# Sheet3.net
KiCad netlist of a schematic drawn in Altium Designer
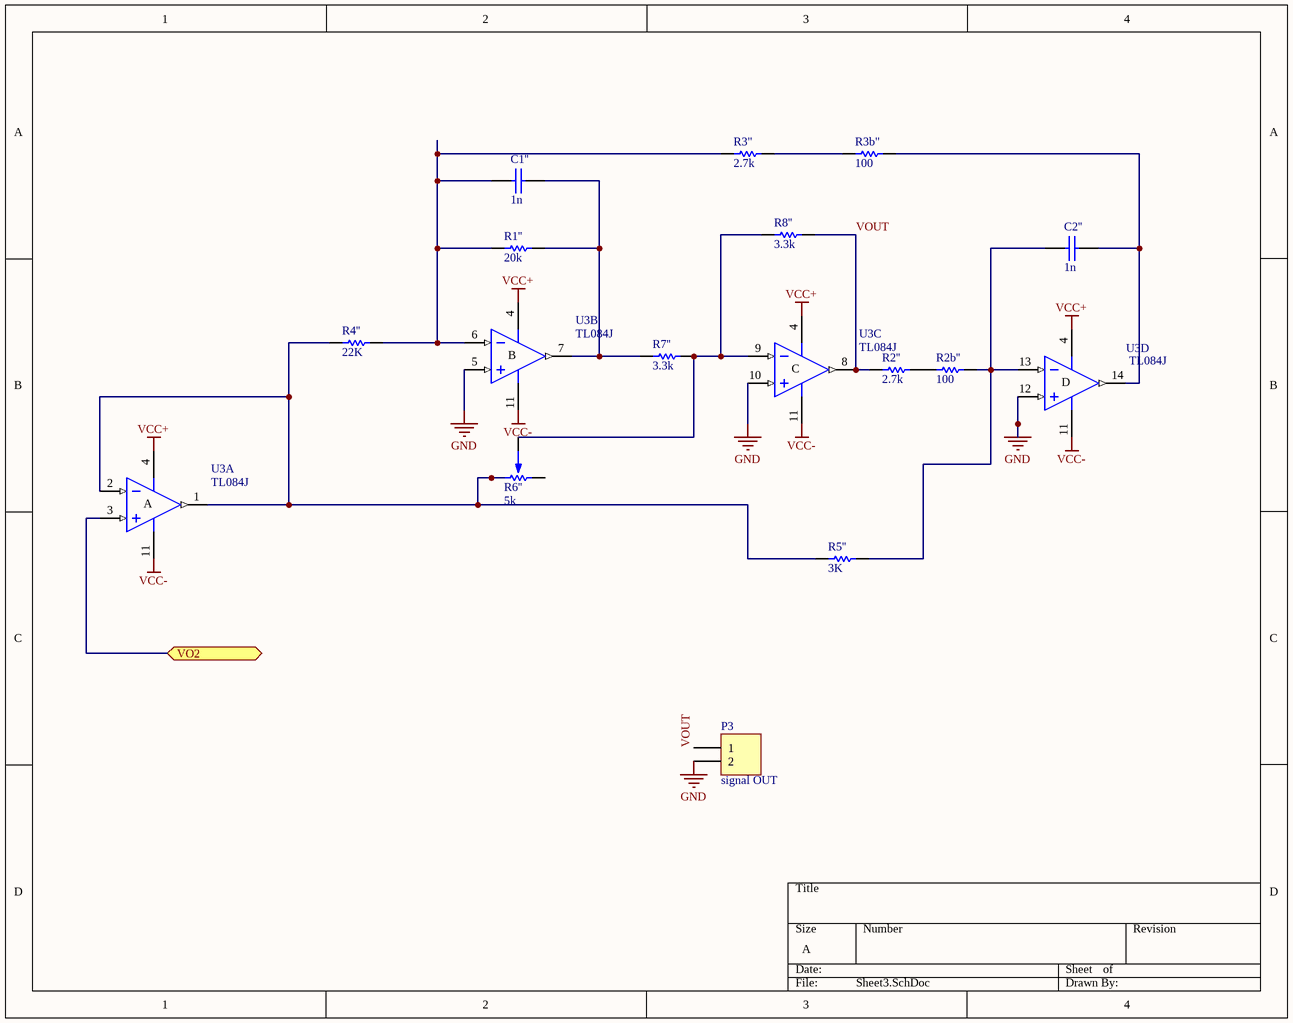
[diagram p0: Sheet3.SchDoc]

(export (version "E")
  (design (tool "Eeschema 10.0.6"))
  (components
    (comp (ref "C1''") (value "1n") (footprint "CAP100") (libsource (lib "LIBEBAL") (part "CAP")))
    (comp (ref "C2''") (value "1n") (footprint "CAP100") (libsource (lib "LIBEBAL") (part "CAP")))
    (comp (ref "P3")
      (value "signal OUT")
      (footprint "HDR1X2")
      (description "Header, 2-Pin")
      (fields (field (name "PUBLISHER") "Altium Limited"))
      (libsource (lib "Miscellaneous Connectors") (part "Header 2"))
    )
    (comp (ref "R1''") (value "20k") (footprint "0805") (libsource (lib "LIBEBAL") (part "RES")))
    (comp (ref "R2''") (value "2.7k") (footprint "0805") (libsource (lib "LIBEBAL") (part "RES")))
    (comp (ref "R2b''") (value "100") (footprint "0805") (libsource (lib "LIBEBAL") (part "RES")))
    (comp (ref "R3\"") (value "2.7k") (footprint "0805") (libsource (lib "LIBEBAL") (part "RES")))
    (comp (ref "R3b\"") (value "100") (footprint "0805") (libsource (lib "LIBEBAL") (part "RES")))
    (comp (ref "R4''") (value "22K") (footprint "0805") (libsource (lib "LIBEBAL") (part "RES")))
    (comp (ref "R5''") (value "3K") (footprint "0805") (libsource (lib "LIBEBAL") (part "RES")))
    (comp (ref "R6''") (value "5k") (footprint "PRESET V") (libsource (lib "LIBEBAL") (part "PRESET")))
    (comp (ref "R7''") (value "3.3k") (footprint "0805") (libsource (lib "LIBEBAL") (part "RES")))
    (comp (ref "R8''") (value "3.3k") (footprint "0805") (libsource (lib "LIBEBAL") (part "RES")))
    (comp (ref "U3")
      (value "TL084J")
      (footprint "J014")
      (description "JFET-Input Operational Amplifier")
      (fields (field (name "PUBLISHER") "Altium Limited"))
      (libsource (lib "TI Operational Amplifier") (part "TL084J"))
    )
  )
  (nets
    (net (code "1") (name "/VO2") (class "Default")
      (node (ref "U3") (pin "3") (pinfunction "IN+_3") (pintype "input"))
    )
    (net (code "2") (name "/VOUT") (class "Default")
      (node (ref "P3") (pin "1") (pinfunction "1_1") (pintype "passive"))
      (node (ref "R2''") (pin "1") (pinfunction "1_1") (pintype "passive"))
      (node (ref "R8''") (pin "2") (pinfunction "2_2") (pintype "passive"))
      (node (ref "U3") (pin "8") (pinfunction "OUT_8") (pintype "output"))
    )
    (net (code "3") (name "GND") (class "Default")
      (node (ref "P3") (pin "2") (pinfunction "2_2") (pintype "passive"))
      (node (ref "U3") (pin "10") (pinfunction "IN+_10") (pintype "input"))
      (node (ref "U3") (pin "12") (pinfunction "IN+_12") (pintype "input"))
      (node (ref "U3") (pin "5") (pinfunction "IN+_5") (pintype "input"))
    )
    (net (code "4") (name "Net-(R2''-Pad2)") (class "Default")
      (node (ref "R2''") (pin "2") (pinfunction "2_2") (pintype "passive"))
      (node (ref "R2b''") (pin "1") (pinfunction "1_1") (pintype "passive"))
    )
    (net (code "5") (name "Net-(R3\"-Pad2)") (class "Default")
      (node (ref "R3\"") (pin "2") (pinfunction "2_2") (pintype "passive"))
      (node (ref "R3b\"") (pin "1") (pinfunction "1_1") (pintype "passive"))
    )
    (net (code "6") (name "Net-(U3A-IN-)") (class "Default")
      (node (ref "R4''") (pin "1") (pinfunction "1_1") (pintype "passive"))
      (node (ref "R5''") (pin "1") (pinfunction "1_1") (pintype "passive"))
      (node (ref "R6''") (pin "1") (pinfunction "1_1") (pintype "passive"))
      (node (ref "U3") (pin "1") (pinfunction "OUT_1") (pintype "output"))
      (node (ref "U3") (pin "2") (pinfunction "IN-_2") (pintype "input"))
    )
    (net (code "7") (name "Net-(U3B-IN-)") (class "Default")
      (node (ref "C1''") (pin "1") (pinfunction "1_1") (pintype "passive"))
      (node (ref "R1''") (pin "1") (pinfunction "1_1") (pintype "passive"))
      (node (ref "R3\"") (pin "1") (pinfunction "1_1") (pintype "passive"))
      (node (ref "R4''") (pin "2") (pinfunction "2_2") (pintype "passive"))
      (node (ref "U3") (pin "6") (pinfunction "IN-_6") (pintype "input"))
    )
    (net (code "8") (name "Net-(U3B-OUT)") (class "Default")
      (node (ref "C1''") (pin "2") (pinfunction "2_2") (pintype "passive"))
      (node (ref "R1''") (pin "2") (pinfunction "2_2") (pintype "passive"))
      (node (ref "R7''") (pin "1") (pinfunction "1_1") (pintype "passive"))
      (node (ref "U3") (pin "7") (pinfunction "OUT_7") (pintype "output"))
    )
    (net (code "9") (name "Net-(U3C-IN-)") (class "Default")
      (node (ref "R6''") (pin "2") (pinfunction "2_2") (pintype "passive"))
      (node (ref "R7''") (pin "2") (pinfunction "2_2") (pintype "passive"))
      (node (ref "R8''") (pin "1") (pinfunction "1_1") (pintype "passive"))
      (node (ref "U3") (pin "9") (pinfunction "IN-_9") (pintype "input"))
    )
    (net (code "10") (name "Net-(U3D-IN-)") (class "Default")
      (node (ref "C2''") (pin "1") (pinfunction "1_1") (pintype "passive"))
      (node (ref "R2b''") (pin "2") (pinfunction "2_2") (pintype "passive"))
      (node (ref "R5''") (pin "2") (pinfunction "2_2") (pintype "passive"))
      (node (ref "U3") (pin "13") (pinfunction "IN-_13") (pintype "input"))
    )
    (net (code "11") (name "Net-(U3D-OUT)") (class "Default")
      (node (ref "C2''") (pin "2") (pinfunction "2_2") (pintype "passive"))
      (node (ref "R3b\"") (pin "2") (pinfunction "2_2") (pintype "passive"))
      (node (ref "U3") (pin "14") (pinfunction "OUT_14") (pintype "output"))
    )
    (net (code "12") (name "VCC+") (class "Default")
      (node (ref "U3") (pin "4") (pinfunction "V+_4") (pintype "power_in"))
    )
    (net (code "13") (name "VCC-") (class "Default")
      (node (ref "U3") (pin "11") (pinfunction "V-_11") (pintype "power_in"))
    )
    (net (code "14") (name "unconnected-(R6''-Pad3)") (class "Default")
      (node (ref "R6''") (pin "3") (pinfunction "3_3") (pintype "passive"))
    )
  )
)
